# RADM-RadioModule-S01-V00.net
KiCad netlist of a schematic drawn in Altium Designer
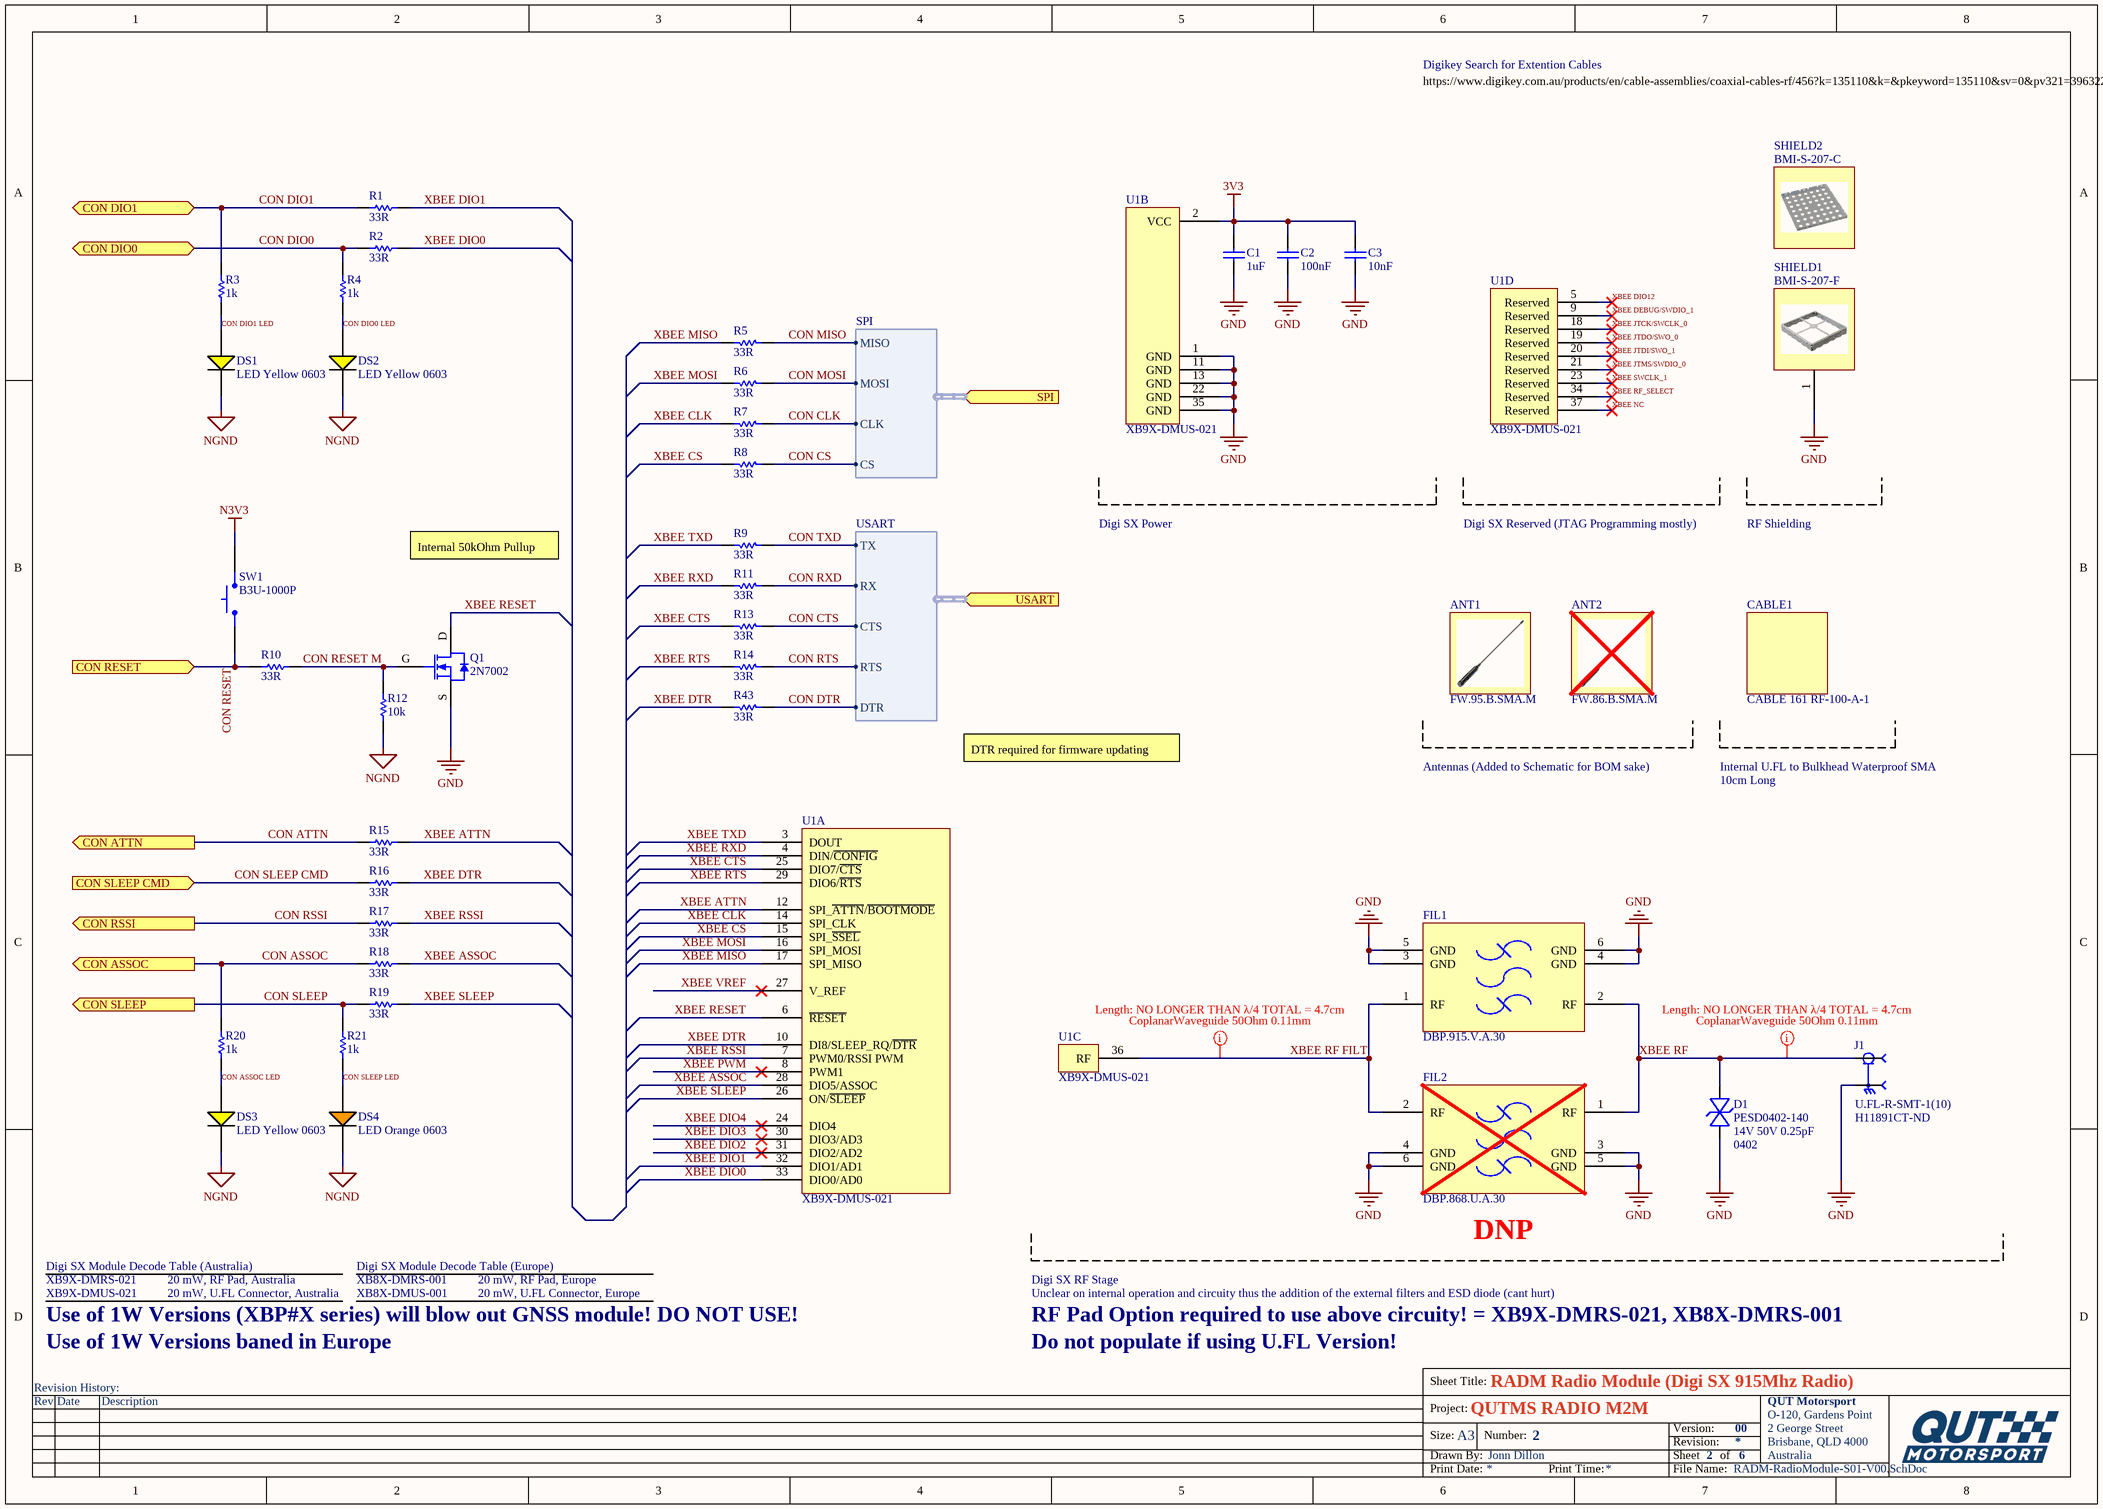
[diagram p0: RADM-RadioModule-S01-V00.SchDoc]

(export (version "E")
  (design (tool "Eeschema 10.0.6"))
  (components
    (comp (ref "ANT1")
      (value "FW.95.B.SMA.M")
      (description "915MHz ISM Whip, Straight RF Antenna 2.7dBi SMA Male Connector Mount")
      (libsource (lib "QUTMS_RadioLibrary") (part "FW.95.B.SMA.M"))
    )
    (comp (ref "ANT2")
      (value "FW.86.B.SMA.M")
      (description "868MHz ISM Whip, Straight RF Antenna 2.8dBi SMA Male Connector Mount")
      (libsource (lib "QUTMS_RadioLibrary") (part "FW.86.B.SMA.M"))
    )
    (comp (ref "C1")
      (value "1uF")
      (footprint "Cap_Ceramic_0603")
      (description "Capacitor, Ceramic, SMD, 1uF, 25V, 5%, X7R, 0603")
      (libsource (lib "StandardCapacitors") (part "1uF 25V 5% X7R 0603"))
    )
    (comp (ref "C2")
      (value "100nF")
      (footprint "Cap_Ceramic_0603")
      (description "Capacitor, Ceramic, SMD, 100nF, 50V, 5%, X7R, 0603")
      (libsource (lib "StandardCapacitors") (part "100nF 50V 5% X7R 0603"))
    )
    (comp (ref "C3")
      (value "10nF")
      (footprint "Cap_Ceramic_0603")
      (description "Capacitor, Ceramic, SMD, 10nF, 50V, 5%, X7R, 0603")
      (libsource (lib "StandardCapacitors") (part "10nF 50V 5% X7R 0603"))
    )
    (comp (ref "CABLE1")
      (value "CABLE 161 RF-100-A-1")
      (description "Cable Assembly Coaxial U.FL (UMCC), IPEX MHF1 to SMA Female to Female RG-178 3.937\" (100.00mm)")
      (libsource (lib "QUTMS_RadioLibrary") (part "CABLE 161 RF-100-A-1"))
    )
    (comp (ref "D1")
      (value "PESD0402-140")
      (footprint "FERRITEBEAD_0402")
      (description "40V Clamp Ipp Tvs Diode Surface Mount 0402")
      (libsource (lib "QUTMS_RadioLibrary") (part "PESD0402-140"))
    )
    (comp (ref "DS1")
      (value "LED Yellow 0603")
      (footprint "LED YELLOW 0603")
      (libsource (lib "QUTMS_LEDLibrary") (part "LED Yellow 0603"))
    )
    (comp (ref "DS2")
      (value "LED Yellow 0603")
      (footprint "LED YELLOW 0603")
      (libsource (lib "QUTMS_LEDLibrary") (part "LED Yellow 0603"))
    )
    (comp (ref "DS3")
      (value "LED Yellow 0603")
      (footprint "LED YELLOW 0603")
      (libsource (lib "QUTMS_LEDLibrary") (part "LED Yellow 0603"))
    )
    (comp (ref "DS4")
      (value "LED Orange 0603")
      (footprint "LED ORANGE 0603")
      (libsource (lib "QUTMS_LEDLibrary") (part "LED Orange 0603"))
    )
    (comp (ref "FIL1")
      (value "DBP.915.V.A.30")
      (footprint "TAOGLAS 915MHZ FILTER")
      (description "915MHz Frequency Band Pass RF Filter (Radio Frequency) 5MHz Bandwidth 3.2dB 2-SMD, No Lead")
      (libsource (lib "QUTMS_RadioLibrary") (part "DBP.915.V.A.30"))
    )
    (comp (ref "FIL2")
      (value "DBP.868.U.A.30")
      (footprint "TAOGLAS 868MHZ FILTER")
      (description "868MHz Frequency Band Pass RF Filter (Radio Frequency) 4MHz Bandwidth 3dB 2-SMD, No Lead")
      (libsource (lib "QUTMS_RadioLibrary") (part "DBP.868.U.A.30"))
    )
    (comp (ref "J1")
      (value "U.FL-R-SMT-1(10)")
      (footprint "U.FL-R-SMT HIROSE")
      (description "U.FL (UMCC) Connector Receptacle, Male Pin 50Ohm Surface Mount Solder,  H11891CT-ND")
      (libsource (lib "QUTMS_RadioLibrary") (part "U.FL-R-SMT-1(10)"))
    )
    (comp (ref "Q1")
      (value "2N7002")
      (footprint "SOT23-3")
      (libsource (lib "QUTMS_MOSFETLibrary") (part "2N7002"))
    )
    (comp (ref "R1")
      (value "33R")
      (footprint "Res_ThinFilm_0603")
      (description "Resistor, SMD, 33R, 0.1W, 5%, 0603")
      (libsource (lib "StandardResistors") (part "33R 5% 0603"))
    )
    (comp (ref "R2")
      (value "33R")
      (footprint "Res_ThinFilm_0603")
      (description "Resistor, SMD, 33R, 0.1W, 5%, 0603")
      (libsource (lib "StandardResistors") (part "33R 5% 0603"))
    )
    (comp (ref "R3")
      (value "1k")
      (footprint "Res_ThinFilm_0603")
      (description "Resistor, SMD, 1k, 0.1W, 5%, 0603")
      (libsource (lib "StandardResistors") (part "1k 5% 0603"))
    )
    (comp (ref "R4")
      (value "1k")
      (footprint "Res_ThinFilm_0603")
      (description "Resistor, SMD, 1k, 0.1W, 5%, 0603")
      (libsource (lib "StandardResistors") (part "1k 5% 0603"))
    )
    (comp (ref "R5")
      (value "33R")
      (footprint "Res_ThinFilm_0603")
      (description "Resistor, SMD, 33R, 0.1W, 5%, 0603")
      (libsource (lib "StandardResistors") (part "33R 5% 0603"))
    )
    (comp (ref "R6")
      (value "33R")
      (footprint "Res_ThinFilm_0603")
      (description "Resistor, SMD, 33R, 0.1W, 5%, 0603")
      (libsource (lib "StandardResistors") (part "33R 5% 0603"))
    )
    (comp (ref "R7")
      (value "33R")
      (footprint "Res_ThinFilm_0603")
      (description "Resistor, SMD, 33R, 0.1W, 5%, 0603")
      (libsource (lib "StandardResistors") (part "33R 5% 0603"))
    )
    (comp (ref "R8")
      (value "33R")
      (footprint "Res_ThinFilm_0603")
      (description "Resistor, SMD, 33R, 0.1W, 5%, 0603")
      (libsource (lib "StandardResistors") (part "33R 5% 0603"))
    )
    (comp (ref "R9")
      (value "33R")
      (footprint "Res_ThinFilm_0603")
      (description "Resistor, SMD, 33R, 0.1W, 5%, 0603")
      (libsource (lib "StandardResistors") (part "33R 5% 0603"))
    )
    (comp (ref "R10")
      (value "33R")
      (footprint "Res_ThinFilm_0603")
      (description "Resistor, SMD, 33R, 0.1W, 5%, 0603")
      (libsource (lib "StandardResistors") (part "33R 5% 0603"))
    )
    (comp (ref "R11")
      (value "33R")
      (footprint "Res_ThinFilm_0603")
      (description "Resistor, SMD, 33R, 0.1W, 5%, 0603")
      (libsource (lib "StandardResistors") (part "33R 5% 0603"))
    )
    (comp (ref "R12")
      (value "10k")
      (footprint "Res_ThinFilm_0603")
      (description "Resistor, SMD, 10k, 0.1W, 5%, 0603")
      (libsource (lib "StandardResistors") (part "10k 5% 0603"))
    )
    (comp (ref "R13")
      (value "33R")
      (footprint "Res_ThinFilm_0603")
      (description "Resistor, SMD, 33R, 0.1W, 5%, 0603")
      (libsource (lib "StandardResistors") (part "33R 5% 0603"))
    )
    (comp (ref "R14")
      (value "33R")
      (footprint "Res_ThinFilm_0603")
      (description "Resistor, SMD, 33R, 0.1W, 5%, 0603")
      (libsource (lib "StandardResistors") (part "33R 5% 0603"))
    )
    (comp (ref "R15")
      (value "33R")
      (footprint "Res_ThinFilm_0603")
      (description "Resistor, SMD, 33R, 0.1W, 5%, 0603")
      (libsource (lib "StandardResistors") (part "33R 5% 0603"))
    )
    (comp (ref "R16")
      (value "33R")
      (footprint "Res_ThinFilm_0603")
      (description "Resistor, SMD, 33R, 0.1W, 5%, 0603")
      (libsource (lib "StandardResistors") (part "33R 5% 0603"))
    )
    (comp (ref "R17")
      (value "33R")
      (footprint "Res_ThinFilm_0603")
      (description "Resistor, SMD, 33R, 0.1W, 5%, 0603")
      (libsource (lib "StandardResistors") (part "33R 5% 0603"))
    )
    (comp (ref "R18")
      (value "33R")
      (footprint "Res_ThinFilm_0603")
      (description "Resistor, SMD, 33R, 0.1W, 5%, 0603")
      (libsource (lib "StandardResistors") (part "33R 5% 0603"))
    )
    (comp (ref "R19")
      (value "33R")
      (footprint "Res_ThinFilm_0603")
      (description "Resistor, SMD, 33R, 0.1W, 5%, 0603")
      (libsource (lib "StandardResistors") (part "33R 5% 0603"))
    )
    (comp (ref "R20")
      (value "1k")
      (footprint "Res_ThinFilm_0603")
      (description "Resistor, SMD, 1k, 0.1W, 5%, 0603")
      (libsource (lib "StandardResistors") (part "1k 5% 0603"))
    )
    (comp (ref "R21")
      (value "1k")
      (footprint "Res_ThinFilm_0603")
      (description "Resistor, SMD, 1k, 0.1W, 5%, 0603")
      (libsource (lib "StandardResistors") (part "1k 5% 0603"))
    )
    (comp (ref "R43")
      (value "33R")
      (footprint "Res_ThinFilm_0603")
      (description "Resistor, SMD, 33R, 0.1W, 5%, 0603")
      (libsource (lib "StandardResistors") (part "33R 5% 0603"))
    )
    (comp (ref "SHIELD1")
      (value "BMI-S-207-F")
      (footprint "BMI-S-207-F")
      (description "RF Shield Frame 1.747\" (44.37mm) X 1.747\" (44.37mm) Solder")
      (libsource (lib "QUTMS_RadioLibrary") (part "BMI-S-207-F"))
    )
    (comp (ref "SHIELD2")
      (value "BMI-S-207-C")
      (description "RF Shield Cover 1.344\" (34.14mm) X 1.468\" (37.29mm) Vent Holes in Pattern Snap Fit")
      (libsource (lib "QUTMS_RadioLibrary") (part "BMI-S-207-C"))
    )
    (comp (ref "SW1")
      (value "B3U-1000P")
      (footprint "BTN B3U-1000P")
      (description "Omron B3U-1000P Ultra Miniture Switch")
      (libsource (lib "QUTMS_SwitchLibrary") (part "BTN B3U-1000P"))
    )
    (comp (ref "U1")
      (value "XB9X-DMUS-021")
      (footprint "XBee_1W_Base")
      (description "General ISM < 1GHz Transceiver Module 902MHz ~ 928MHz Antenna Not Included, U.FL Surface Mount")
      (libsource (lib "QUTMS_RadioLibrary") (part "XB9X-DMUS-021"))
    )
  )
  (nets
    (net (code "3") (name "/CON ASSOC") (class "Default")
      (node (ref "R18") (pin "1") (pinfunction "1_1") (pintype "passive"))
      (node (ref "R20") (pin "2") (pinfunction "2_2") (pintype "passive"))
    )
    (net (code "4") (name "/CON ASSOC LED") (class "Default")
      (node (ref "DS3") (pin "1") (pinfunction "A_1") (pintype "passive"))
      (node (ref "R20") (pin "1") (pinfunction "1_1") (pintype "passive"))
    )
    (net (code "5") (name "/CON ATTN") (class "Default")
      (node (ref "R15") (pin "1") (pinfunction "1_1") (pintype "passive"))
    )
    (net (code "6") (name "/CON CLK") (class "Default")
      (node (ref "R7") (pin "1") (pinfunction "1_1") (pintype "passive"))
    )
    (net (code "7") (name "/CON CS") (class "Default")
      (node (ref "R8") (pin "1") (pinfunction "1_1") (pintype "passive"))
    )
    (net (code "8") (name "/CON CTS") (class "Default")
      (node (ref "R13") (pin "1") (pinfunction "1_1") (pintype "passive"))
    )
    (net (code "9") (name "/CON DIO0") (class "Default")
      (node (ref "R2") (pin "1") (pinfunction "1_1") (pintype "passive"))
      (node (ref "R4") (pin "2") (pinfunction "2_2") (pintype "passive"))
    )
    (net (code "10") (name "/CON DIO0 LED") (class "Default")
      (node (ref "DS2") (pin "1") (pinfunction "A_1") (pintype "passive"))
      (node (ref "R4") (pin "1") (pinfunction "1_1") (pintype "passive"))
    )
    (net (code "11") (name "/CON DIO1") (class "Default")
      (node (ref "R1") (pin "1") (pinfunction "1_1") (pintype "passive"))
      (node (ref "R3") (pin "2") (pinfunction "2_2") (pintype "passive"))
    )
    (net (code "12") (name "/CON DIO1 LED") (class "Default")
      (node (ref "DS1") (pin "1") (pinfunction "A_1") (pintype "passive"))
      (node (ref "R3") (pin "1") (pinfunction "1_1") (pintype "passive"))
    )
    (net (code "13") (name "/CON DTR") (class "Default")
      (node (ref "R43") (pin "1") (pinfunction "1_1") (pintype "passive"))
    )
    (net (code "14") (name "/CON MISO") (class "Default")
      (node (ref "R5") (pin "1") (pinfunction "1_1") (pintype "passive"))
    )
    (net (code "15") (name "/CON MOSI") (class "Default")
      (node (ref "R6") (pin "1") (pinfunction "1_1") (pintype "passive"))
    )
    (net (code "16") (name "/CON RESET") (class "Default")
      (node (ref "R10") (pin "1") (pinfunction "1_1") (pintype "passive"))
      (node (ref "SW1") (pin "1") (pinfunction "1_1") (pintype "passive"))
    )
    (net (code "17") (name "/CON RESET M") (class "Default")
      (node (ref "Q1") (pin "G") (pinfunction "G_G") (pintype "passive"))
      (node (ref "R10") (pin "2") (pinfunction "2_2") (pintype "passive"))
      (node (ref "R12") (pin "2") (pinfunction "2_2") (pintype "passive"))
    )
    (net (code "18") (name "/CON RSSI") (class "Default")
      (node (ref "R17") (pin "1") (pinfunction "1_1") (pintype "passive"))
    )
    (net (code "19") (name "/CON RTS") (class "Default")
      (node (ref "R14") (pin "1") (pinfunction "1_1") (pintype "passive"))
    )
    (net (code "20") (name "/CON RXD") (class "Default")
      (node (ref "R11") (pin "1") (pinfunction "1_1") (pintype "passive"))
    )
    (net (code "21") (name "/CON SLEEP") (class "Default")
      (node (ref "R19") (pin "1") (pinfunction "1_1") (pintype "passive"))
      (node (ref "R21") (pin "2") (pinfunction "2_2") (pintype "passive"))
    )
    (net (code "22") (name "/CON SLEEP CMD") (class "Default")
      (node (ref "R16") (pin "1") (pinfunction "1_1") (pintype "passive"))
    )
    (net (code "23") (name "/CON SLEEP LED") (class "Default")
      (node (ref "DS4") (pin "1") (pinfunction "A_1") (pintype "passive"))
      (node (ref "R21") (pin "1") (pinfunction "1_1") (pintype "passive"))
    )
    (net (code "24") (name "/CON TXD") (class "Default")
      (node (ref "R9") (pin "1") (pinfunction "1_1") (pintype "passive"))
    )
    (net (code "25") (name "/XBEE ASSOC") (class "Default")
      (node (ref "R18") (pin "2") (pinfunction "2_2") (pintype "passive"))
      (node (ref "U1") (pin "28") (pinfunction "DIO5/ASSOC_28") (pintype "passive"))
    )
    (net (code "26") (name "/XBEE ATTN") (class "Default")
      (node (ref "R15") (pin "2") (pinfunction "2_2") (pintype "passive"))
      (node (ref "U1") (pin "12") (pinfunction "SPI_~{ATTN}/~{BOOTMODE}_12") (pintype "passive"))
    )
    (net (code "27") (name "/XBEE CLK") (class "Default")
      (node (ref "R7") (pin "2") (pinfunction "2_2") (pintype "passive"))
      (node (ref "U1") (pin "14") (pinfunction "SPI_CLK_14") (pintype "passive"))
    )
    (net (code "28") (name "/XBEE CS") (class "Default")
      (node (ref "R8") (pin "2") (pinfunction "2_2") (pintype "passive"))
      (node (ref "U1") (pin "15") (pinfunction "SPI_~{SSEL}_15") (pintype "passive"))
    )
    (net (code "29") (name "/XBEE CTS") (class "Default")
      (node (ref "R13") (pin "2") (pinfunction "2_2") (pintype "passive"))
      (node (ref "U1") (pin "25") (pinfunction "DIO7/~{CTS}_25") (pintype "passive"))
    )
    (net (code "30") (name "/XBEE DEBUG{slash}SWDIO_1") (class "Default")
      (node (ref "U1") (pin "9") (pinfunction "Reserved_9") (pintype "passive+no_connect"))
    )
    (net (code "31") (name "/XBEE DIO0") (class "Default")
      (node (ref "R2") (pin "2") (pinfunction "2_2") (pintype "passive"))
      (node (ref "U1") (pin "33") (pinfunction "DIO0/AD0_33") (pintype "passive"))
    )
    (net (code "32") (name "/XBEE DIO1") (class "Default")
      (node (ref "R1") (pin "2") (pinfunction "2_2") (pintype "passive"))
      (node (ref "U1") (pin "32") (pinfunction "DIO1/AD1_32") (pintype "passive"))
    )
    (net (code "33") (name "/XBEE DIO2") (class "Default")
      (node (ref "U1") (pin "31") (pinfunction "DIO2/AD2_31") (pintype "passive+no_connect"))
    )
    (net (code "34") (name "/XBEE DIO3") (class "Default")
      (node (ref "U1") (pin "30") (pinfunction "DIO3/AD3_30") (pintype "passive+no_connect"))
    )
    (net (code "35") (name "/XBEE DIO4") (class "Default")
      (node (ref "U1") (pin "24") (pinfunction "DIO4_24") (pintype "passive+no_connect"))
    )
    (net (code "36") (name "/XBEE DIO12") (class "Default")
      (node (ref "U1") (pin "5") (pinfunction "Reserved_5") (pintype "passive+no_connect"))
    )
    (net (code "37") (name "/XBEE DTR") (class "Default")
      (node (ref "R16") (pin "2") (pinfunction "2_2") (pintype "passive"))
      (node (ref "R43") (pin "2") (pinfunction "2_2") (pintype "passive"))
      (node (ref "U1") (pin "10") (pinfunction "DI8/SLEEP_RQ/~{DTR}_10") (pintype "passive"))
    )
    (net (code "38") (name "/XBEE JTCK{slash}SWCLK_0") (class "Default")
      (node (ref "U1") (pin "18") (pinfunction "Reserved_18") (pintype "passive+no_connect"))
    )
    (net (code "39") (name "/XBEE JTDI{slash}SWO_1") (class "Default")
      (node (ref "U1") (pin "20") (pinfunction "Reserved_20") (pintype "passive+no_connect"))
    )
    (net (code "40") (name "/XBEE JTDO{slash}SWO_0") (class "Default")
      (node (ref "U1") (pin "19") (pinfunction "Reserved_19") (pintype "passive+no_connect"))
    )
    (net (code "41") (name "/XBEE JTMS{slash}SWDIO_0") (class "Default")
      (node (ref "U1") (pin "21") (pinfunction "Reserved_21") (pintype "passive+no_connect"))
    )
    (net (code "42") (name "/XBEE MISO") (class "Default")
      (node (ref "R5") (pin "2") (pinfunction "2_2") (pintype "passive"))
      (node (ref "U1") (pin "17") (pinfunction "SPI_MISO_17") (pintype "passive"))
    )
    (net (code "43") (name "/XBEE MOSI") (class "Default")
      (node (ref "R6") (pin "2") (pinfunction "2_2") (pintype "passive"))
      (node (ref "U1") (pin "16") (pinfunction "SPI_MOSI_16") (pintype "passive"))
    )
    (net (code "44") (name "/XBEE NC") (class "Default")
      (node (ref "U1") (pin "37") (pinfunction "Reserved_37") (pintype "passive+no_connect"))
    )
    (net (code "45") (name "/XBEE PWM") (class "Default")
      (node (ref "U1") (pin "8") (pinfunction "PWM1_8") (pintype "passive+no_connect"))
    )
    (net (code "46") (name "/XBEE RESET") (class "Default")
      (node (ref "Q1") (pin "D") (pinfunction "D_D") (pintype "passive"))
      (node (ref "U1") (pin "6") (pinfunction "~{RESET}_6") (pintype "passive"))
    )
    (net (code "47") (name "/XBEE RF") (class "Default")
      (node (ref "D1") (pin "2") (pinfunction "Cathode_2") (pintype "passive"))
      (node (ref "FIL1") (pin "2") (pinfunction "RF_2") (pintype "passive"))
      (node (ref "FIL2") (pin "1") (pinfunction "RF_1") (pintype "passive"))
      (node (ref "J1") (pin "1") (pinfunction "SIG_1") (pintype "passive"))
    )
    (net (code "48") (name "/XBEE RF FILT") (class "Default")
      (node (ref "FIL1") (pin "1") (pinfunction "RF_1") (pintype "passive"))
      (node (ref "FIL2") (pin "2") (pinfunction "RF_2") (pintype "passive"))
      (node (ref "U1") (pin "36") (pinfunction "RF_36") (pintype "passive"))
    )
    (net (code "49") (name "/XBEE RF_SELECT") (class "Default")
      (node (ref "U1") (pin "34") (pinfunction "Reserved_34") (pintype "passive+no_connect"))
    )
    (net (code "50") (name "/XBEE RSSI") (class "Default")
      (node (ref "R17") (pin "2") (pinfunction "2_2") (pintype "passive"))
      (node (ref "U1") (pin "7") (pinfunction "PWM0/RSSI_PWM_7") (pintype "passive"))
    )
    (net (code "51") (name "/XBEE RTS") (class "Default")
      (node (ref "R14") (pin "2") (pinfunction "2_2") (pintype "passive"))
      (node (ref "U1") (pin "29") (pinfunction "DIO6/~{RTS}_29") (pintype "passive"))
    )
    (net (code "52") (name "/XBEE RXD") (class "Default")
      (node (ref "R11") (pin "2") (pinfunction "2_2") (pintype "passive"))
      (node (ref "U1") (pin "4") (pinfunction "DIN/~{CONFIG}_4") (pintype "passive"))
    )
    (net (code "53") (name "/XBEE SLEEP") (class "Default")
      (node (ref "R19") (pin "2") (pinfunction "2_2") (pintype "passive"))
      (node (ref "U1") (pin "26") (pinfunction "ON/~{SLEEP}_26") (pintype "passive"))
    )
    (net (code "54") (name "/XBEE SWCLK_1") (class "Default")
      (node (ref "U1") (pin "23") (pinfunction "Reserved_23") (pintype "passive+no_connect"))
    )
    (net (code "55") (name "/XBEE TXD") (class "Default")
      (node (ref "R9") (pin "2") (pinfunction "2_2") (pintype "passive"))
      (node (ref "U1") (pin "3") (pinfunction "DOUT_3") (pintype "passive"))
    )
    (net (code "56") (name "/XBEE VREF") (class "Default")
      (node (ref "U1") (pin "27") (pinfunction "V_REF_27") (pintype "passive+no_connect"))
    )
    (net (code "59") (name "3V3") (class "Default")
      (node (ref "C1") (pin "2") (pinfunction "2_2") (pintype "passive"))
      (node (ref "C2") (pin "2") (pinfunction "2_2") (pintype "passive"))
      (node (ref "C3") (pin "2") (pinfunction "2_2") (pintype "passive"))
      (node (ref "U1") (pin "2") (pinfunction "VCC_2") (pintype "passive"))
    )
    (net (code "60") (name "GND") (class "Default")
      (node (ref "C1") (pin "1") (pinfunction "1_1") (pintype "passive"))
      (node (ref "C2") (pin "1") (pinfunction "1_1") (pintype "passive"))
      (node (ref "C3") (pin "1") (pinfunction "1_1") (pintype "passive"))
      (node (ref "D1") (pin "1") (pinfunction "Anode_1") (pintype "passive"))
      (node (ref "FIL1") (pin "3") (pinfunction "GND_3") (pintype "passive"))
      (node (ref "FIL1") (pin "4") (pinfunction "GND_4") (pintype "passive"))
      (node (ref "FIL1") (pin "5") (pinfunction "GND_5") (pintype "passive"))
      (node (ref "FIL1") (pin "6") (pinfunction "GND_6") (pintype "passive"))
      (node (ref "FIL2") (pin "3") (pinfunction "GND_3") (pintype "passive"))
      (node (ref "FIL2") (pin "4") (pinfunction "GND_4") (pintype "passive"))
      (node (ref "FIL2") (pin "5") (pinfunction "GND_5") (pintype "passive"))
      (node (ref "FIL2") (pin "6") (pinfunction "GND_6") (pintype "passive"))
      (node (ref "J1") (pin "2") (pinfunction "GND_2") (pintype "passive"))
      (node (ref "Q1") (pin "S") (pinfunction "S_S") (pintype "passive"))
      (node (ref "SHIELD1") (pin "1") (pinfunction "1_1") (pintype "passive"))
      (node (ref "U1") (pin "1") (pinfunction "GND_1") (pintype "passive"))
      (node (ref "U1") (pin "11") (pinfunction "GND_11") (pintype "passive"))
      (node (ref "U1") (pin "13") (pinfunction "GND_13") (pintype "passive"))
      (node (ref "U1") (pin "22") (pinfunction "GND_22") (pintype "passive"))
      (node (ref "U1") (pin "35") (pinfunction "GND_35") (pintype "passive"))
    )
    (net (code "61") (name "N3V3") (class "Default")
      (node (ref "SW1") (pin "2") (pinfunction "2_2") (pintype "passive"))
    )
    (net (code "62") (name "NGND") (class "Default")
      (node (ref "DS1") (pin "2") (pinfunction "C_2") (pintype "passive"))
      (node (ref "DS2") (pin "2") (pinfunction "C_2") (pintype "passive"))
      (node (ref "DS3") (pin "2") (pinfunction "C_2") (pintype "passive"))
      (node (ref "DS4") (pin "2") (pinfunction "C_2") (pintype "passive"))
      (node (ref "R12") (pin "1") (pinfunction "1_1") (pintype "passive"))
    )
  )
)
